# Customised_arduino.net
KiCad netlist of a schematic drawn in EAGLE
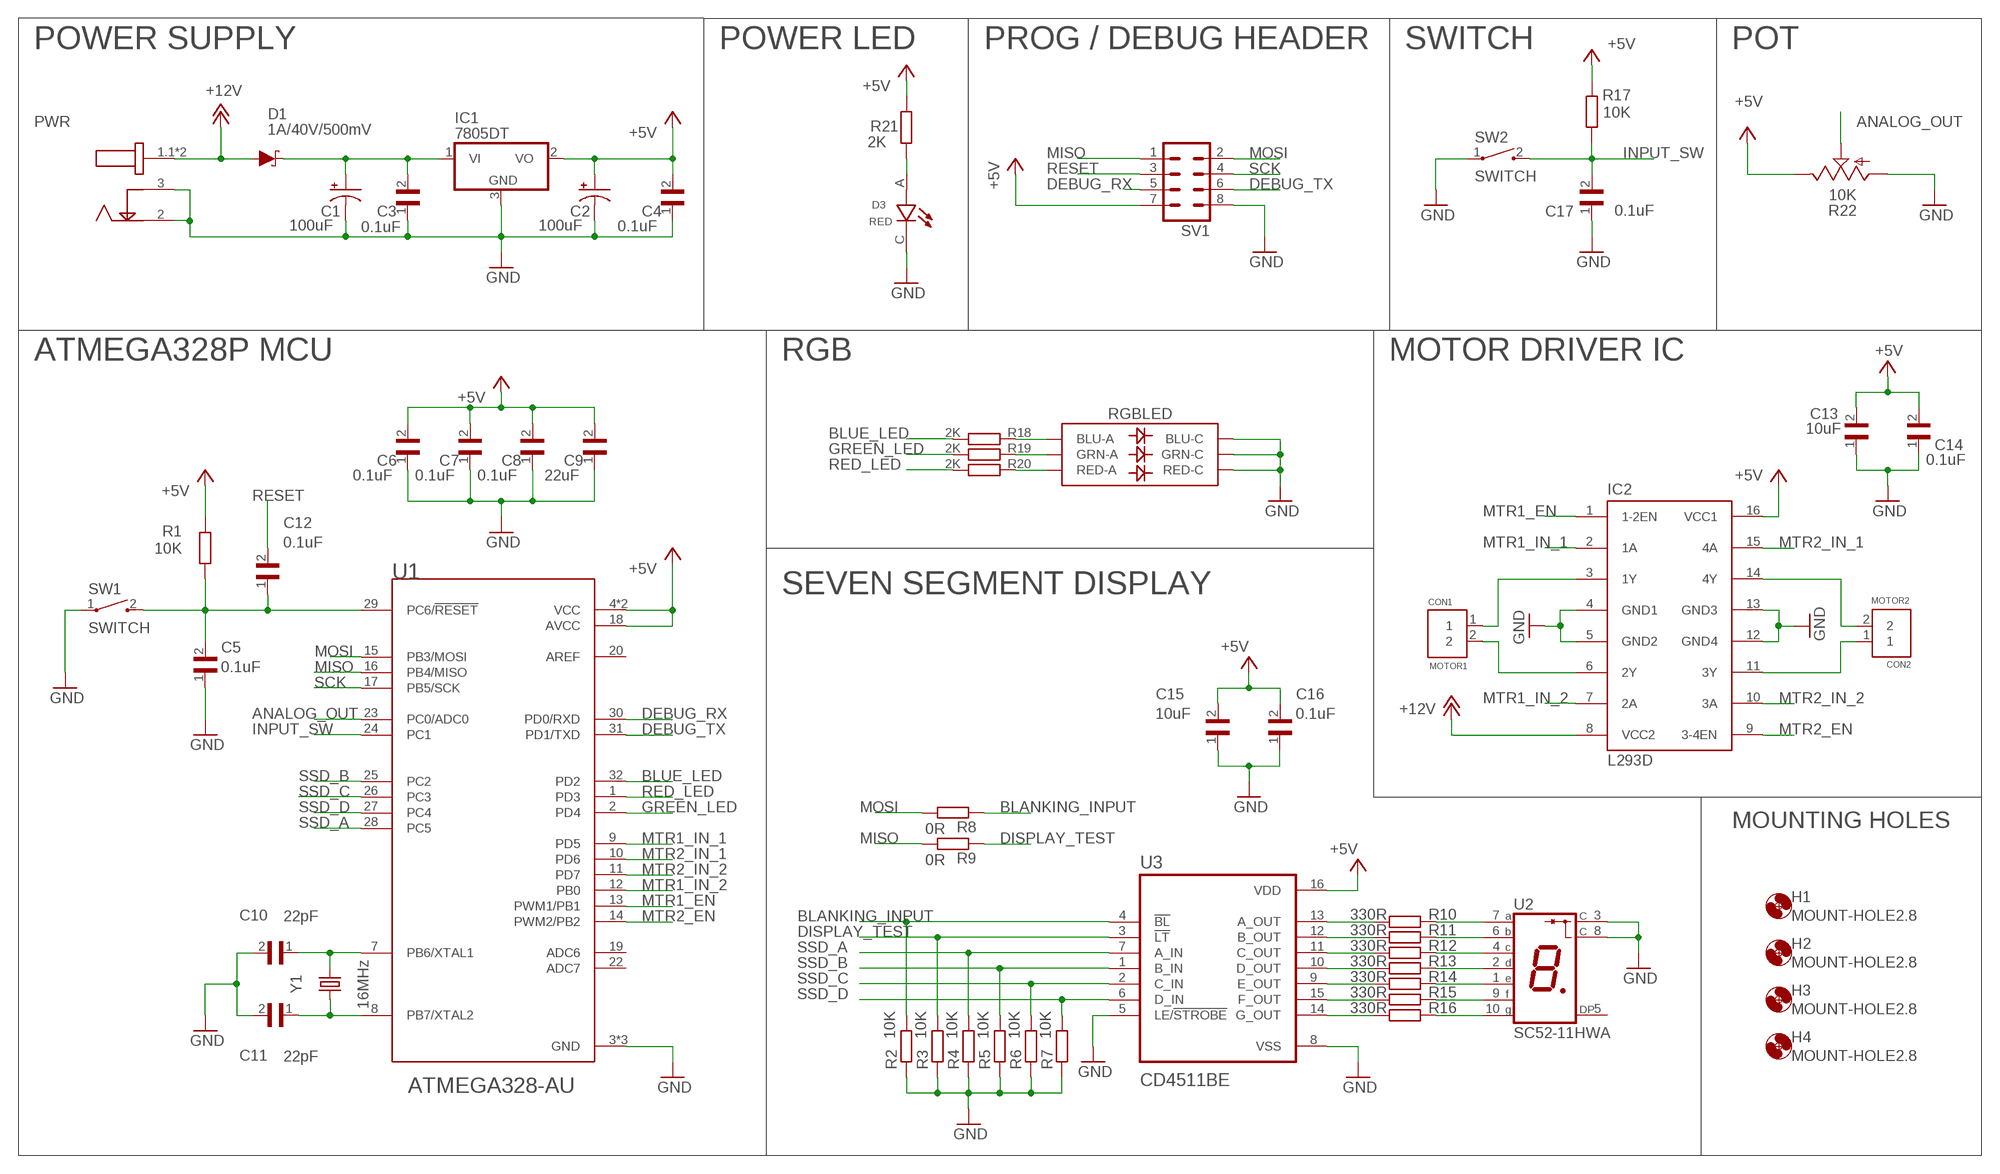
[diagram p0: schematic, sheet 1]

(export (version "E")
  (design (tool "Eeschema 10.0.6"))
  (components
    (comp (ref "C1")
      (value "100uF")
      (footprint "eagle-import:CPOL-RADIAL-2.5MM-6.5MM")
      (libsource (lib "eagle-import") (part "100UF-POLAR-RADIAL-2.5MM-25V-20%"))
    )
    (comp (ref "C2")
      (value "100uF")
      (footprint "eagle-import:CPOL-RADIAL-2.5MM-6.5MM")
      (libsource (lib "eagle-import") (part "100UF-POLAR-RADIAL-2.5MM-25V-20%"))
    )
    (comp (ref "C3")
      (value "0.1uF")
      (footprint "eagle-import:C0603")
      (fields (field (name "MF") "TDK") (field (name "MP") "CGA3E2X7R1H104K080AA"))
      (libsource (lib "eagle-import") (part "CAPACITOR"))
    )
    (comp (ref "C4")
      (value "0.1uF")
      (footprint "eagle-import:C0603")
      (fields (field (name "MF") "TDK") (field (name "MP") "CGA3E2X7R1H104K080AA"))
      (libsource (lib "eagle-import") (part "CAPACITOR"))
    )
    (comp (ref "C5")
      (value "0.1uF")
      (footprint "eagle-import:C0603")
      (fields (field (name "MF") "TDK") (field (name "MP") "CGA3E2X7R1H104K080AA"))
      (libsource (lib "eagle-import") (part "CAPACITOR"))
    )
    (comp (ref "C6")
      (value "0.1uF")
      (footprint "eagle-import:C0603")
      (fields (field (name "MF") "TDK") (field (name "MP") "CGA3E2X7R1H104K080AA"))
      (libsource (lib "eagle-import") (part "CAPACITOR"))
    )
    (comp (ref "C7")
      (value "0.1uF")
      (footprint "eagle-import:C0603")
      (fields (field (name "MF") "TDK") (field (name "MP") "CGA3E2X7R1H104K080AA"))
      (libsource (lib "eagle-import") (part "CAPACITOR"))
    )
    (comp (ref "C8")
      (value "0.1uF")
      (footprint "eagle-import:C0603")
      (fields (field (name "MF") "TDK") (field (name "MP") "CGA3E2X7R1H104K080AA"))
      (libsource (lib "eagle-import") (part "CAPACITOR"))
    )
    (comp (ref "C9")
      (value "22uF")
      (footprint "eagle-import:C0603")
      (fields (field (name "MF") "TDK") (field (name "MP") "CGA3E2X7R1H104K080AA"))
      (libsource (lib "eagle-import") (part "CAPACITOR"))
    )
    (comp (ref "C10")
      (value "22pF")
      (footprint "eagle-import:C0603")
      (fields (field (name "MF") "TDK") (field (name "MP") "CGA3E2X7R1H104K080AA"))
      (libsource (lib "eagle-import") (part "CAPACITOR"))
    )
    (comp (ref "C11")
      (value "22pF")
      (footprint "eagle-import:C0603")
      (fields (field (name "MF") "TDK") (field (name "MP") "CGA3E2X7R1H104K080AA"))
      (libsource (lib "eagle-import") (part "CAPACITOR"))
    )
    (comp (ref "C12")
      (value "0.1uF")
      (footprint "eagle-import:C0603")
      (fields (field (name "MF") "TDK") (field (name "MP") "CGA3E2X7R1H104K080AA"))
      (libsource (lib "eagle-import") (part "CAPACITOR"))
    )
    (comp (ref "C13")
      (value "10uF")
      (footprint "eagle-import:C0603")
      (fields (field (name "MF") "TDK") (field (name "MP") "CGA3E2X7R1H104K080AA"))
      (libsource (lib "eagle-import") (part "CAPACITOR"))
    )
    (comp (ref "C14")
      (value "0.1uF")
      (footprint "eagle-import:C0603")
      (fields (field (name "MF") "TDK") (field (name "MP") "CGA3E2X7R1H104K080AA"))
      (libsource (lib "eagle-import") (part "CAPACITOR"))
    )
    (comp (ref "C15")
      (value "10uF")
      (footprint "eagle-import:C0603")
      (fields (field (name "MF") "TDK") (field (name "MP") "CGA3E2X7R1H104K080AA"))
      (libsource (lib "eagle-import") (part "CAPACITOR"))
    )
    (comp (ref "C16")
      (value "0.1uF")
      (footprint "eagle-import:C0603")
      (fields (field (name "MF") "TDK") (field (name "MP") "CGA3E2X7R1H104K080AA"))
      (libsource (lib "eagle-import") (part "CAPACITOR"))
    )
    (comp (ref "C17")
      (value "0.1uF")
      (footprint "eagle-import:C0603")
      (fields (field (name "MF") "TDK") (field (name "MP") "CGA3E2X7R1H104K080AA"))
      (libsource (lib "eagle-import") (part "CAPACITOR"))
    )
    (comp (ref "CON1")
      (value "MOTOR1")
      (footprint "eagle-import:CONN_282836-2")
      (fields (field (name "COMMENT") "282836-2") (field (name "MF") "TE Connectivity"))
      (libsource (lib "eagle-import") (part "282836-2"))
    )
    (comp (ref "CON2")
      (value "MOTOR2")
      (footprint "eagle-import:CONN_282836-2")
      (fields (field (name "COMMENT") "282836-2") (field (name "MF") "TE Connectivity"))
      (libsource (lib "eagle-import") (part "282836-2"))
    )
    (comp (ref "D1")
      (value "1A/40V/500mV")
      (footprint "eagle-import:SMA-DIODE")
      (libsource (lib "eagle-import") (part "DIODE-SCHOTTKY-SS14"))
    )
    (comp (ref "D3")
      (value "RED")
      (footprint "eagle-import:LEDC1608X65N")
      (fields (field (name "MF") "Lite-On") (field (name "MP") "LTW-C191TLA"))
      (libsource (lib "eagle-import") (part "LTW-C191TLA"))
    )
    (comp (ref "H1")
      (value "MOUNT-HOLE2.8")
      (footprint "eagle-import:2,8")
      (libsource (lib "eagle-import") (part "MOUNT-HOLE2.8"))
    )
    (comp (ref "H2")
      (value "MOUNT-HOLE2.8")
      (footprint "eagle-import:2,8")
      (libsource (lib "eagle-import") (part "MOUNT-HOLE2.8"))
    )
    (comp (ref "H3")
      (value "MOUNT-HOLE2.8")
      (footprint "eagle-import:2,8")
      (libsource (lib "eagle-import") (part "MOUNT-HOLE2.8"))
    )
    (comp (ref "H4")
      (value "MOUNT-HOLE2.8")
      (footprint "eagle-import:2,8")
      (libsource (lib "eagle-import") (part "MOUNT-HOLE2.8"))
    )
    (comp (ref "IC1")
      (value "7805DT")
      (footprint "eagle-import:TO252")
      (libsource (lib "eagle-import") (part "78DT05"))
    )
    (comp (ref "IC2")
      (value "L293D")
      (footprint "eagle-import:DIL16")
      (libsource (lib "eagle-import") (part "L293D"))
    )
    (comp (ref "PWR")
      (value "DCJ200-05-A-XX-X_REVA")
      (footprint "eagle-import:GCT_DCJ200-05-A-XX-X_REVA")
      (fields (field (name "MF") "Global Connector Technology") (field (name "MP") "DCJ200-05-A-K1-A"))
      (libsource (lib "eagle-import") (part "DCJ200-05-A-XX-X_REVA"))
    )
    (comp (ref "R1")
      (value "10K")
      (footprint "eagle-import:R0603")
      (fields (field (name "MF") "Yageo"))
      (libsource (lib "eagle-import") (part "RESISTOR"))
    )
    (comp (ref "R2")
      (value "10K")
      (footprint "eagle-import:R0603")
      (fields (field (name "MF") "Yageo"))
      (libsource (lib "eagle-import") (part "RESISTOR"))
    )
    (comp (ref "R3")
      (value "10K")
      (footprint "eagle-import:R0603")
      (fields (field (name "MF") "Yageo"))
      (libsource (lib "eagle-import") (part "RESISTOR"))
    )
    (comp (ref "R4")
      (value "10K")
      (footprint "eagle-import:R0603")
      (fields (field (name "MF") "Yageo"))
      (libsource (lib "eagle-import") (part "RESISTOR"))
    )
    (comp (ref "R5")
      (value "10K")
      (footprint "eagle-import:R0603")
      (fields (field (name "MF") "Yageo"))
      (libsource (lib "eagle-import") (part "RESISTOR"))
    )
    (comp (ref "R6")
      (value "10K")
      (footprint "eagle-import:R0603")
      (fields (field (name "MF") "Yageo"))
      (libsource (lib "eagle-import") (part "RESISTOR"))
    )
    (comp (ref "R7")
      (value "10K")
      (footprint "eagle-import:R0603")
      (fields (field (name "MF") "Yageo"))
      (libsource (lib "eagle-import") (part "RESISTOR"))
    )
    (comp (ref "R8")
      (value "0R")
      (footprint "eagle-import:R0603")
      (fields (field (name "MF") "Yageo"))
      (libsource (lib "eagle-import") (part "RESISTOR"))
    )
    (comp (ref "R9")
      (value "0R")
      (footprint "eagle-import:R0603")
      (fields (field (name "MF") "Yageo"))
      (libsource (lib "eagle-import") (part "RESISTOR"))
    )
    (comp (ref "R10")
      (value "330R")
      (footprint "eagle-import:R0603")
      (fields (field (name "MF") "Yageo"))
      (libsource (lib "eagle-import") (part "RESISTOR"))
    )
    (comp (ref "R11")
      (value "330R")
      (footprint "eagle-import:R0603")
      (fields (field (name "MF") "Yageo"))
      (libsource (lib "eagle-import") (part "RESISTOR"))
    )
    (comp (ref "R12")
      (value "330R")
      (footprint "eagle-import:R0603")
      (fields (field (name "MF") "Yageo"))
      (libsource (lib "eagle-import") (part "RESISTOR"))
    )
    (comp (ref "R13")
      (value "330R")
      (footprint "eagle-import:R0603")
      (fields (field (name "MF") "Yageo"))
      (libsource (lib "eagle-import") (part "RESISTOR"))
    )
    (comp (ref "R14")
      (value "330R")
      (footprint "eagle-import:R0603")
      (fields (field (name "MF") "Yageo"))
      (libsource (lib "eagle-import") (part "RESISTOR"))
    )
    (comp (ref "R15")
      (value "330R")
      (footprint "eagle-import:R0603")
      (fields (field (name "MF") "Yageo"))
      (libsource (lib "eagle-import") (part "RESISTOR"))
    )
    (comp (ref "R16")
      (value "330R")
      (footprint "eagle-import:R0603")
      (fields (field (name "MF") "Yageo"))
      (libsource (lib "eagle-import") (part "RESISTOR"))
    )
    (comp (ref "R17")
      (value "10K")
      (footprint "eagle-import:R0603")
      (fields (field (name "MF") "Yageo"))
      (libsource (lib "eagle-import") (part "RESISTOR"))
    )
    (comp (ref "R18")
      (value "2K")
      (footprint "eagle-import:R0603")
      (fields (field (name "MF") "Yageo"))
      (libsource (lib "eagle-import") (part "RESISTOR"))
    )
    (comp (ref "R19")
      (value "2K")
      (footprint "eagle-import:R0603")
      (fields (field (name "MF") "Yageo"))
      (libsource (lib "eagle-import") (part "RESISTOR"))
    )
    (comp (ref "R20")
      (value "2K")
      (footprint "eagle-import:R0603")
      (fields (field (name "MF") "Yageo"))
      (libsource (lib "eagle-import") (part "RESISTOR"))
    )
    (comp (ref "R21")
      (value "2K")
      (footprint "eagle-import:R0603")
      (fields (field (name "MF") "Yageo"))
      (libsource (lib "eagle-import") (part "RESISTOR"))
    )
    (comp (ref "R22")
      (value "10K")
      (footprint "eagle-import:S64W")
      (libsource (lib "eagle-import") (part "TRIM_US-S64W"))
    )
    (comp (ref "RGBLED")
      (value "LED-RGBNO_IC")
      (footprint "eagle-import:LED-TRICOLOR-5050")
      (libsource (lib "eagle-import") (part "LED-RGBNO_IC"))
    )
    (comp (ref "SV1")
      (value "MA04-2")
      (footprint "eagle-import:MA04-2")
      (libsource (lib "eagle-import") (part "MA04-2"))
    )
    (comp (ref "SW1")
      (value "SWITCH")
      (footprint "eagle-import:SW_1437566-3")
      (fields (field (name "COMMENT") "1437566-3") (field (name "MF") "TE Connectivity"))
      (libsource (lib "eagle-import") (part "1437566-3"))
    )
    (comp (ref "SW2")
      (value "SWITCH")
      (footprint "eagle-import:SW_1437566-3")
      (fields (field (name "COMMENT") "1437566-3") (field (name "MF") "TE Connectivity"))
      (libsource (lib "eagle-import") (part "1437566-3"))
    )
    (comp (ref "U1")
      (value "ATMEGA328-AU")
      (footprint "eagle-import:QFP80P900X900X120-32N")
      (fields (field (name "MF") "Microchip"))
      (libsource (lib "eagle-import") (part "ATMEGA328-AU"))
    )
    (comp (ref "U2")
      (value "SC52-11HWA")
      (footprint "eagle-import:LED_SC52-11HWA")
      (fields (field (name "MF") "Kingbright"))
      (libsource (lib "eagle-import") (part "SC52-11HWA"))
    )
    (comp (ref "U3")
      (value "CD4511BE")
      (footprint "eagle-import:DIP794W45P254L1969H508Q16")
      (fields (field (name "MF") "Texas Instruments"))
      (libsource (lib "eagle-import") (part "CD4511BE"))
    )
    (comp (ref "Y1")
      (value "16MHz")
      (footprint "eagle-import:HC49US")
      (libsource (lib "eagle-import") (part "CRYSTAL-16MHZPTH-HC49US"))
    )
  )
  (nets
    (net (code "1") (name "+5V") (class "Default")
      (node (ref "C13") (pin "2") (pinfunction "2_2") (pintype "passive"))
      (node (ref "C14") (pin "2") (pinfunction "2_2") (pintype "passive"))
      (node (ref "C15") (pin "2") (pinfunction "2_2") (pintype "passive"))
      (node (ref "C16") (pin "2") (pinfunction "2_2") (pintype "passive"))
      (node (ref "C2") (pin "1") (pinfunction "+_1") (pintype "passive"))
      (node (ref "C4") (pin "2") (pinfunction "2_2") (pintype "passive"))
      (node (ref "C6") (pin "2") (pinfunction "2_2") (pintype "passive"))
      (node (ref "C7") (pin "2") (pinfunction "2_2") (pintype "passive"))
      (node (ref "C8") (pin "2") (pinfunction "2_2") (pintype "passive"))
      (node (ref "C9") (pin "2") (pinfunction "2_2") (pintype "passive"))
      (node (ref "IC1") (pin "2") (pinfunction "VO_2") (pintype "passive"))
      (node (ref "IC2") (pin "16") (pinfunction "VCC1_16") (pintype "power_in"))
      (node (ref "R1") (pin "2") (pinfunction "2_2") (pintype "passive"))
      (node (ref "R17") (pin "2") (pinfunction "2_2") (pintype "passive"))
      (node (ref "R21") (pin "2") (pinfunction "2_2") (pintype "passive"))
      (node (ref "R22") (pin "E") (pinfunction "E_E") (pintype "passive"))
      (node (ref "SV1") (pin "7") (pinfunction "7_7") (pintype "passive"))
      (node (ref "U1") (pin "18") (pinfunction "AVCC_18") (pintype "power_in"))
      (node (ref "U1") (pin "4") (pinfunction "VCC_4") (pintype "power_in"))
      (node (ref "U1") (pin "6") (pinfunction "VCC_6") (pintype "power_in"))
      (node (ref "U3") (pin "16") (pinfunction "VDD_16") (pintype "power_in"))
    )
    (net (code "2") (name "+12V") (class "Default")
      (node (ref "D1") (pin "A") (pinfunction "A_A") (pintype "passive"))
      (node (ref "IC2") (pin "8") (pinfunction "VCC2_8") (pintype "power_in"))
      (node (ref "PWR") (pin "1.1") (pinfunction "1_1.1") (pintype "passive"))
      (node (ref "PWR") (pin "1.2") (pinfunction "1_1.2") (pintype "passive"))
    )
    (net (code "3") (name "/ANALOG_OUT") (class "Default")
      (node (ref "R22") (pin "S") (pinfunction "S_S") (pintype "passive"))
      (node (ref "U1") (pin "23") (pinfunction "PC0/ADC0_23") (pintype "bidirectional"))
    )
    (net (code "4") (name "/BLANKING_INPUT") (class "Default")
      (node (ref "R2") (pin "2") (pinfunction "2_2") (pintype "passive"))
      (node (ref "R8") (pin "1") (pinfunction "1_1") (pintype "passive"))
      (node (ref "U3") (pin "4") (pinfunction "~{BL}_4") (pintype "input"))
    )
    (net (code "5") (name "/BLUE_LED") (class "Default")
      (node (ref "R18") (pin "2") (pinfunction "2_2") (pintype "passive"))
      (node (ref "U1") (pin "32") (pinfunction "PD2_32") (pintype "bidirectional"))
    )
    (net (code "6") (name "/DEBUG_RX") (class "Default")
      (node (ref "SV1") (pin "5") (pinfunction "5_5") (pintype "passive"))
      (node (ref "U1") (pin "30") (pinfunction "PD0/RXD_30") (pintype "bidirectional"))
    )
    (net (code "7") (name "/DEBUG_TX") (class "Default")
      (node (ref "SV1") (pin "6") (pinfunction "6_6") (pintype "passive"))
      (node (ref "U1") (pin "31") (pinfunction "PD1/TXD_31") (pintype "bidirectional"))
    )
    (net (code "8") (name "/DISPLAY_TEST") (class "Default")
      (node (ref "R3") (pin "2") (pinfunction "2_2") (pintype "passive"))
      (node (ref "R9") (pin "1") (pinfunction "1_1") (pintype "passive"))
      (node (ref "U3") (pin "3") (pinfunction "~{LT}_3") (pintype "input"))
    )
    (net (code "9") (name "/GREEN_LED") (class "Default")
      (node (ref "R19") (pin "2") (pinfunction "2_2") (pintype "passive"))
      (node (ref "U1") (pin "2") (pinfunction "PD4_2") (pintype "bidirectional"))
    )
    (net (code "10") (name "/INPUT_SW") (class "Default")
      (node (ref "C17") (pin "2") (pinfunction "2_2") (pintype "passive"))
      (node (ref "R17") (pin "1") (pinfunction "1_1") (pintype "passive"))
      (node (ref "SW2") (pin "2") (pinfunction "2_2") (pintype "passive"))
      (node (ref "U1") (pin "24") (pinfunction "PC1_24") (pintype "bidirectional"))
    )
    (net (code "11") (name "/MISO") (class "Default")
      (node (ref "R9") (pin "2") (pinfunction "2_2") (pintype "passive"))
      (node (ref "SV1") (pin "1") (pinfunction "1_1") (pintype "passive"))
      (node (ref "U1") (pin "16") (pinfunction "PB4/MISO_16") (pintype "bidirectional"))
    )
    (net (code "12") (name "/MOSI") (class "Default")
      (node (ref "R8") (pin "2") (pinfunction "2_2") (pintype "passive"))
      (node (ref "SV1") (pin "2") (pinfunction "2_2") (pintype "passive"))
      (node (ref "U1") (pin "15") (pinfunction "PB3/MOSI_15") (pintype "bidirectional"))
    )
    (net (code "13") (name "/MTR1_EN") (class "Default")
      (node (ref "IC2") (pin "1") (pinfunction "1-2EN_1") (pintype "input"))
      (node (ref "U1") (pin "13") (pinfunction "PWM1/PB1_13") (pintype "bidirectional"))
    )
    (net (code "14") (name "/MTR1_IN_1") (class "Default")
      (node (ref "IC2") (pin "2") (pinfunction "1A_2") (pintype "input"))
      (node (ref "U1") (pin "9") (pinfunction "PD5_9") (pintype "bidirectional"))
    )
    (net (code "15") (name "/MTR1_IN_2") (class "Default")
      (node (ref "IC2") (pin "7") (pinfunction "2A_7") (pintype "input"))
      (node (ref "U1") (pin "12") (pinfunction "PB0_12") (pintype "bidirectional"))
    )
    (net (code "16") (name "/MTR2_EN") (class "Default")
      (node (ref "IC2") (pin "9") (pinfunction "3-4EN_9") (pintype "input"))
      (node (ref "U1") (pin "14") (pinfunction "PWM2/PB2_14") (pintype "bidirectional"))
    )
    (net (code "17") (name "/MTR2_IN_1") (class "Default")
      (node (ref "IC2") (pin "15") (pinfunction "4A_15") (pintype "input"))
      (node (ref "U1") (pin "10") (pinfunction "PD6_10") (pintype "bidirectional"))
    )
    (net (code "18") (name "/MTR2_IN_2") (class "Default")
      (node (ref "IC2") (pin "10") (pinfunction "3A_10") (pintype "input"))
      (node (ref "U1") (pin "11") (pinfunction "PD7_11") (pintype "bidirectional"))
    )
    (net (code "19") (name "/RED_LED") (class "Default")
      (node (ref "R20") (pin "2") (pinfunction "2_2") (pintype "passive"))
      (node (ref "U1") (pin "1") (pinfunction "PD3_1") (pintype "bidirectional"))
    )
    (net (code "20") (name "/RESET") (class "Default")
      (node (ref "C12") (pin "2") (pinfunction "2_2") (pintype "passive"))
      (node (ref "SV1") (pin "3") (pinfunction "3_3") (pintype "passive"))
    )
    (net (code "21") (name "/SCK") (class "Default")
      (node (ref "SV1") (pin "4") (pinfunction "4_4") (pintype "passive"))
      (node (ref "U1") (pin "17") (pinfunction "PB5/SCK_17") (pintype "bidirectional"))
    )
    (net (code "22") (name "/SSD_A") (class "Default")
      (node (ref "R4") (pin "2") (pinfunction "2_2") (pintype "passive"))
      (node (ref "U1") (pin "28") (pinfunction "PC5_28") (pintype "bidirectional"))
      (node (ref "U3") (pin "7") (pinfunction "A_IN_7") (pintype "input"))
    )
    (net (code "23") (name "/SSD_B") (class "Default")
      (node (ref "R5") (pin "2") (pinfunction "2_2") (pintype "passive"))
      (node (ref "U1") (pin "25") (pinfunction "PC2_25") (pintype "bidirectional"))
      (node (ref "U3") (pin "1") (pinfunction "B_IN_1") (pintype "input"))
    )
    (net (code "24") (name "/SSD_C") (class "Default")
      (node (ref "R6") (pin "2") (pinfunction "2_2") (pintype "passive"))
      (node (ref "U1") (pin "26") (pinfunction "PC3_26") (pintype "bidirectional"))
      (node (ref "U3") (pin "2") (pinfunction "C_IN_2") (pintype "input"))
    )
    (net (code "25") (name "/SSD_D") (class "Default")
      (node (ref "R7") (pin "2") (pinfunction "2_2") (pintype "passive"))
      (node (ref "U1") (pin "27") (pinfunction "PC4_27") (pintype "bidirectional"))
      (node (ref "U3") (pin "6") (pinfunction "D_IN_6") (pintype "input"))
    )
    (net (code "26") (name "GND") (class "Default")
      (node (ref "C1") (pin "2") (pinfunction "-_2") (pintype "passive"))
      (node (ref "C10") (pin "2") (pinfunction "2_2") (pintype "passive"))
      (node (ref "C11") (pin "2") (pinfunction "2_2") (pintype "passive"))
      (node (ref "C13") (pin "1") (pinfunction "1_1") (pintype "passive"))
      (node (ref "C14") (pin "1") (pinfunction "1_1") (pintype "passive"))
      (node (ref "C15") (pin "1") (pinfunction "1_1") (pintype "passive"))
      (node (ref "C16") (pin "1") (pinfunction "1_1") (pintype "passive"))
      (node (ref "C17") (pin "1") (pinfunction "1_1") (pintype "passive"))
      (node (ref "C2") (pin "2") (pinfunction "-_2") (pintype "passive"))
      (node (ref "C3") (pin "1") (pinfunction "1_1") (pintype "passive"))
      (node (ref "C4") (pin "1") (pinfunction "1_1") (pintype "passive"))
      (node (ref "C5") (pin "1") (pinfunction "1_1") (pintype "passive"))
      (node (ref "C6") (pin "1") (pinfunction "1_1") (pintype "passive"))
      (node (ref "C7") (pin "1") (pinfunction "1_1") (pintype "passive"))
      (node (ref "C8") (pin "1") (pinfunction "1_1") (pintype "passive"))
      (node (ref "C9") (pin "1") (pinfunction "1_1") (pintype "passive"))
      (node (ref "D3") (pin "C") (pinfunction "C_C") (pintype "passive"))
      (node (ref "IC1") (pin "3") (pinfunction "GND_3") (pintype "passive"))
      (node (ref "IC2") (pin "12") (pinfunction "GND4_12") (pintype "power_in"))
      (node (ref "IC2") (pin "13") (pinfunction "GND3_13") (pintype "power_in"))
      (node (ref "IC2") (pin "4") (pinfunction "GND1_4") (pintype "power_in"))
      (node (ref "IC2") (pin "5") (pinfunction "GND2_5") (pintype "power_in"))
      (node (ref "PWR") (pin "2") (pinfunction "2_2") (pintype "passive"))
      (node (ref "PWR") (pin "3") (pinfunction "3_3") (pintype "passive"))
      (node (ref "R2") (pin "1") (pinfunction "1_1") (pintype "passive"))
      (node (ref "R22") (pin "A") (pinfunction "A_A") (pintype "passive"))
      (node (ref "R3") (pin "1") (pinfunction "1_1") (pintype "passive"))
      (node (ref "R4") (pin "1") (pinfunction "1_1") (pintype "passive"))
      (node (ref "R5") (pin "1") (pinfunction "1_1") (pintype "passive"))
      (node (ref "R6") (pin "1") (pinfunction "1_1") (pintype "passive"))
      (node (ref "R7") (pin "1") (pinfunction "1_1") (pintype "passive"))
      (node (ref "RGBLED") (pin "4") (pinfunction "BLU-C_4") (pintype "bidirectional"))
      (node (ref "RGBLED") (pin "5") (pinfunction "RED-C_5") (pintype "bidirectional"))
      (node (ref "RGBLED") (pin "6") (pinfunction "GRN-C_6") (pintype "bidirectional"))
      (node (ref "SV1") (pin "8") (pinfunction "8_8") (pintype "passive"))
      (node (ref "SW1") (pin "1") (pinfunction "1_1") (pintype "passive"))
      (node (ref "SW2") (pin "1") (pinfunction "1_1") (pintype "passive"))
      (node (ref "U1") (pin "21") (pinfunction "GND_21") (pintype "power_in"))
      (node (ref "U1") (pin "3") (pinfunction "GND_3") (pintype "power_in"))
      (node (ref "U1") (pin "5") (pinfunction "GND_5") (pintype "power_in"))
      (node (ref "U2") (pin "3") (pinfunction "C_3") (pintype "passive"))
      (node (ref "U2") (pin "8") (pinfunction "C_8") (pintype "passive"))
      (node (ref "U3") (pin "5") (pinfunction "LE/~{STROBE}_5") (pintype "input"))
      (node (ref "U3") (pin "8") (pinfunction "VSS_8") (pintype "power_in"))
    )
    (net (code "27") (name "Net-(C1-+)") (class "Default")
      (node (ref "C1") (pin "1") (pinfunction "+_1") (pintype "passive"))
      (node (ref "C3") (pin "2") (pinfunction "2_2") (pintype "passive"))
      (node (ref "D1") (pin "C") (pinfunction "C_C") (pintype "passive"))
      (node (ref "IC1") (pin "1") (pinfunction "VI_1") (pintype "input"))
    )
    (net (code "28") (name "Net-(D3-PadA)") (class "Default")
      (node (ref "D3") (pin "A") (pinfunction "A_A") (pintype "passive"))
      (node (ref "R21") (pin "1") (pinfunction "1_1") (pintype "passive"))
    )
    (net (code "29") (name "Net-(IC2-1Y)") (class "Default")
      (node (ref "CON1") (pin "1") (pinfunction "1_1") (pintype "passive"))
      (node (ref "IC2") (pin "3") (pinfunction "1Y_3") (pintype "output"))
    )
    (net (code "30") (name "Net-(IC2-2Y)") (class "Default")
      (node (ref "CON1") (pin "2") (pinfunction "2_2") (pintype "passive"))
      (node (ref "IC2") (pin "6") (pinfunction "2Y_6") (pintype "output"))
    )
    (net (code "31") (name "Net-(IC2-3Y)") (class "Default")
      (node (ref "CON2") (pin "1") (pinfunction "1_1") (pintype "passive"))
      (node (ref "IC2") (pin "11") (pinfunction "3Y_11") (pintype "output"))
    )
    (net (code "32") (name "Net-(IC2-4Y)") (class "Default")
      (node (ref "CON2") (pin "2") (pinfunction "2_2") (pintype "passive"))
      (node (ref "IC2") (pin "14") (pinfunction "4Y_14") (pintype "output"))
    )
    (net (code "33") (name "Net-(R12-Pad1)") (class "Default")
      (node (ref "R12") (pin "1") (pinfunction "1_1") (pintype "passive"))
      (node (ref "U2") (pin "4") (pinfunction "C_4") (pintype "passive"))
    )
    (net (code "34") (name "Net-(RGBLED-BLU-A)") (class "Default")
      (node (ref "R18") (pin "1") (pinfunction "1_1") (pintype "passive"))
      (node (ref "RGBLED") (pin "3") (pinfunction "BLU-A_3") (pintype "bidirectional"))
    )
    (net (code "35") (name "Net-(RGBLED-GRN-A)") (class "Default")
      (node (ref "R19") (pin "1") (pinfunction "1_1") (pintype "passive"))
      (node (ref "RGBLED") (pin "1") (pinfunction "GRN-A_1") (pintype "bidirectional"))
    )
    (net (code "36") (name "Net-(RGBLED-RED-A)") (class "Default")
      (node (ref "R20") (pin "1") (pinfunction "1_1") (pintype "passive"))
      (node (ref "RGBLED") (pin "2") (pinfunction "RED-A_2") (pintype "bidirectional"))
    )
    (net (code "37") (name "Net-(U1-PB6{slash}XTAL1)") (class "Default")
      (node (ref "C10") (pin "1") (pinfunction "1_1") (pintype "passive"))
      (node (ref "U1") (pin "7") (pinfunction "PB6/XTAL1_7") (pintype "bidirectional"))
      (node (ref "Y1") (pin "2") (pinfunction "2_2") (pintype "passive"))
    )
    (net (code "38") (name "Net-(U1-PB7{slash}XTAL2)") (class "Default")
      (node (ref "C11") (pin "1") (pinfunction "1_1") (pintype "passive"))
      (node (ref "U1") (pin "8") (pinfunction "PB7/XTAL2_8") (pintype "bidirectional"))
      (node (ref "Y1") (pin "1") (pinfunction "1_1") (pintype "passive"))
    )
    (net (code "39") (name "Net-(U1-PC6{slash}~{RESET})") (class "Default")
      (node (ref "C12") (pin "1") (pinfunction "1_1") (pintype "passive"))
      (node (ref "C5") (pin "2") (pinfunction "2_2") (pintype "passive"))
      (node (ref "R1") (pin "1") (pinfunction "1_1") (pintype "passive"))
      (node (ref "SW1") (pin "2") (pinfunction "2_2") (pintype "passive"))
      (node (ref "U1") (pin "29") (pinfunction "PC6/~{RESET}_29") (pintype "bidirectional"))
    )
    (net (code "40") (name "Net-(U2-A)") (class "Default")
      (node (ref "R10") (pin "1") (pinfunction "1_1") (pintype "passive"))
      (node (ref "U2") (pin "7") (pinfunction "A_7") (pintype "passive"))
    )
    (net (code "41") (name "Net-(U2-B)") (class "Default")
      (node (ref "R11") (pin "1") (pinfunction "1_1") (pintype "passive"))
      (node (ref "U2") (pin "6") (pinfunction "B_6") (pintype "passive"))
    )
    (net (code "42") (name "Net-(U2-D)") (class "Default")
      (node (ref "R13") (pin "1") (pinfunction "1_1") (pintype "passive"))
      (node (ref "U2") (pin "2") (pinfunction "D_2") (pintype "passive"))
    )
    (net (code "43") (name "Net-(U2-E)") (class "Default")
      (node (ref "R14") (pin "1") (pinfunction "1_1") (pintype "passive"))
      (node (ref "U2") (pin "1") (pinfunction "E_1") (pintype "passive"))
    )
    (net (code "44") (name "Net-(U2-F)") (class "Default")
      (node (ref "R15") (pin "1") (pinfunction "1_1") (pintype "passive"))
      (node (ref "U2") (pin "9") (pinfunction "F_9") (pintype "passive"))
    )
    (net (code "45") (name "Net-(U2-G)") (class "Default")
      (node (ref "R16") (pin "1") (pinfunction "1_1") (pintype "passive"))
      (node (ref "U2") (pin "10") (pinfunction "G_10") (pintype "passive"))
    )
    (net (code "46") (name "Net-(U3-A_OUT)") (class "Default")
      (node (ref "R10") (pin "2") (pinfunction "2_2") (pintype "passive"))
      (node (ref "U3") (pin "13") (pinfunction "A_OUT_13") (pintype "output"))
    )
    (net (code "47") (name "Net-(U3-B_OUT)") (class "Default")
      (node (ref "R11") (pin "2") (pinfunction "2_2") (pintype "passive"))
      (node (ref "U3") (pin "12") (pinfunction "B_OUT_12") (pintype "output"))
    )
    (net (code "48") (name "Net-(U3-C_OUT)") (class "Default")
      (node (ref "R12") (pin "2") (pinfunction "2_2") (pintype "passive"))
      (node (ref "U3") (pin "11") (pinfunction "C_OUT_11") (pintype "output"))
    )
    (net (code "49") (name "Net-(U3-D_OUT)") (class "Default")
      (node (ref "R13") (pin "2") (pinfunction "2_2") (pintype "passive"))
      (node (ref "U3") (pin "10") (pinfunction "D_OUT_10") (pintype "output"))
    )
    (net (code "50") (name "Net-(U3-E_OUT)") (class "Default")
      (node (ref "R14") (pin "2") (pinfunction "2_2") (pintype "passive"))
      (node (ref "U3") (pin "9") (pinfunction "E_OUT_9") (pintype "output"))
    )
    (net (code "51") (name "Net-(U3-F_OUT)") (class "Default")
      (node (ref "R15") (pin "2") (pinfunction "2_2") (pintype "passive"))
      (node (ref "U3") (pin "15") (pinfunction "F_OUT_15") (pintype "output"))
    )
    (net (code "52") (name "Net-(U3-G_OUT)") (class "Default")
      (node (ref "R16") (pin "2") (pinfunction "2_2") (pintype "passive"))
      (node (ref "U3") (pin "14") (pinfunction "G_OUT_14") (pintype "output"))
    )
    (net (code "53") (name "unconnected-(U1-ADC6-Pad19)") (class "Default")
      (node (ref "U1") (pin "19") (pinfunction "ADC6_19") (pintype "bidirectional"))
    )
    (net (code "54") (name "unconnected-(U1-ADC7-Pad22)") (class "Default")
      (node (ref "U1") (pin "22") (pinfunction "ADC7_22") (pintype "bidirectional"))
    )
    (net (code "55") (name "unconnected-(U1-AREF-Pad20)") (class "Default")
      (node (ref "U1") (pin "20") (pinfunction "AREF_20") (pintype "input"))
    )
    (net (code "56") (name "unconnected-(U2-DP-Pad5)") (class "Default")
      (node (ref "U2") (pin "5") (pinfunction "DP_5") (pintype "passive"))
    )
  )
)
